# 04ddr3.net
KiCad netlist of a schematic drawn in Altium Designer
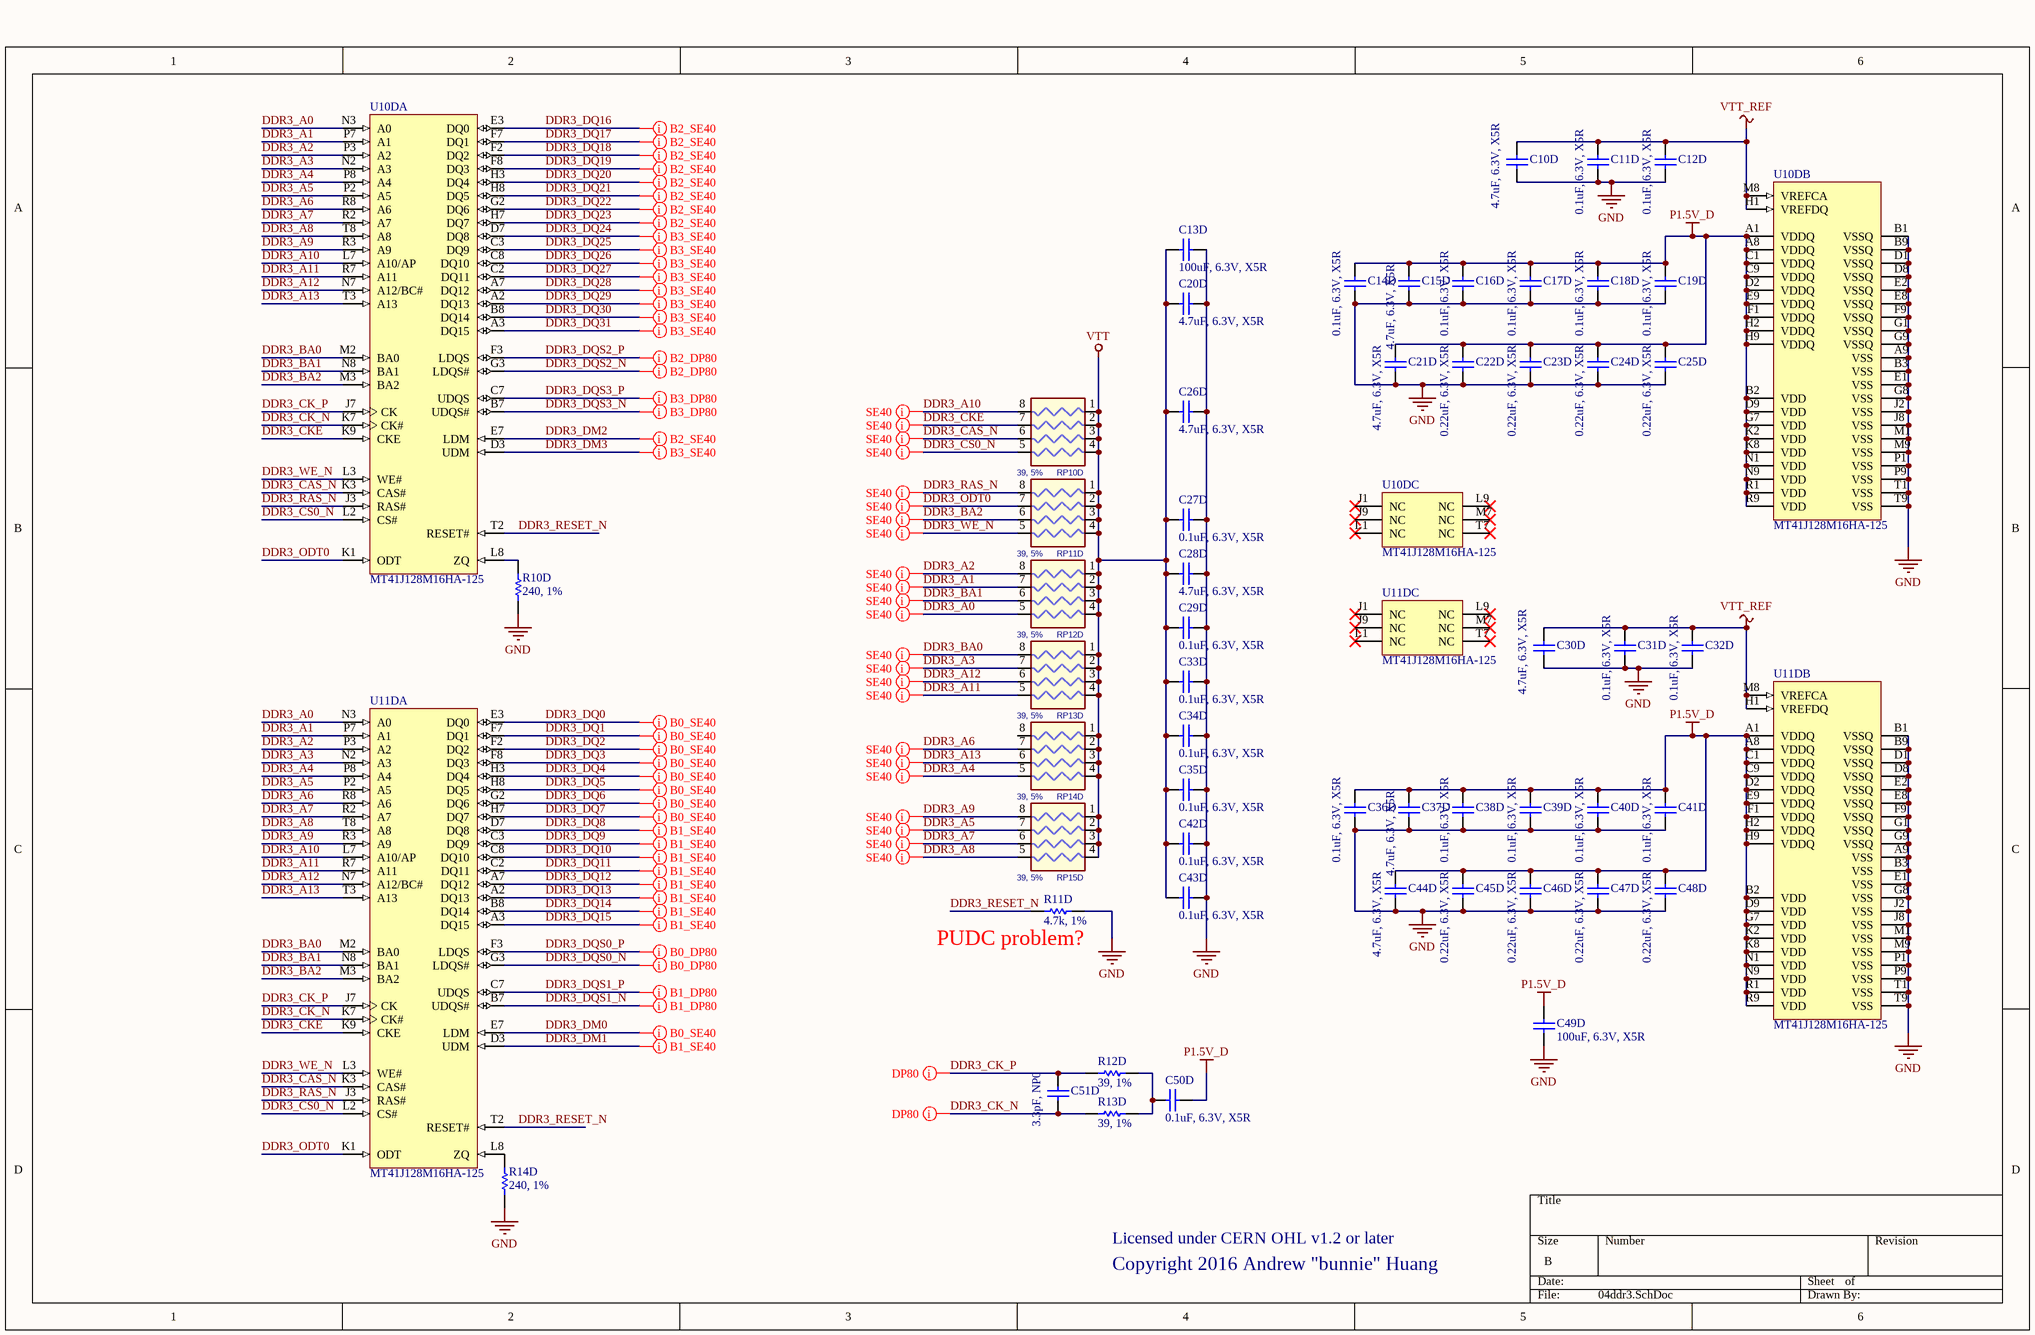
[diagram p0: 04ddr3.SchDoc]

(export (version "E")
  (design (tool "Eeschema 10.0.6"))
  (components
    (comp (ref "C10D")
      (value "4.7uF, 6.3V, X5R")
      (footprint "CAPC1005N")
      (description "Capacitor (Semiconductor SIM Model)")
      (fields (field (name "MPN") "CL05A475MQ5NQNC"))
      (libsource (lib "Miscellaneous Devices") (part "Cap Semi"))
    )
    (comp (ref "C11D")
      (value "0.1uF, 6.3V, X5R")
      (footprint "CAPC0603X03L")
      (description "Capacitor (Semiconductor SIM Model)")
      (fields (field (name "MPN") "CL03A104KQ3NNNC"))
      (libsource (lib "Miscellaneous Devices") (part "Cap Semi"))
    )
    (comp (ref "C12D")
      (value "0.1uF, 6.3V, X5R")
      (footprint "CAPC0603X03L")
      (description "Capacitor (Semiconductor SIM Model)")
      (fields (field (name "MPN") "CL03A104KQ3NNNC"))
      (libsource (lib "Miscellaneous Devices") (part "Cap Semi"))
    )
    (comp (ref "C13D")
      (value "100uF, 6.3V, X5R")
      (footprint "CAPC3216N")
      (description "Capacitor (Semiconductor SIM Model)")
      (fields (field (name "MPN") "CL31A107MQHNNNE"))
      (libsource (lib "Miscellaneous Devices") (part "Cap Semi"))
    )
    (comp (ref "C14D")
      (value "0.1uF, 6.3V, X5R")
      (footprint "CAPC0603X03L")
      (description "Capacitor (Semiconductor SIM Model)")
      (fields (field (name "MPN") "CL03A104KQ3NNNC"))
      (libsource (lib "Miscellaneous Devices") (part "Cap Semi"))
    )
    (comp (ref "C15D")
      (value "4.7uF, 6.3V, X5R")
      (footprint "CAPC1005N")
      (description "Capacitor (Semiconductor SIM Model)")
      (fields (field (name "MPN") "CL05A475MQ5NQNC"))
      (libsource (lib "Miscellaneous Devices") (part "Cap Semi"))
    )
    (comp (ref "C16D")
      (value "0.1uF, 6.3V, X5R")
      (footprint "CAPC0603X03L")
      (description "Capacitor (Semiconductor SIM Model)")
      (fields (field (name "MPN") "CL03A104KQ3NNNC"))
      (libsource (lib "Miscellaneous Devices") (part "Cap Semi"))
    )
    (comp (ref "C17D")
      (value "0.1uF, 6.3V, X5R")
      (footprint "CAPC0603X03L")
      (description "Capacitor (Semiconductor SIM Model)")
      (fields (field (name "MPN") "CL03A104KQ3NNNC"))
      (libsource (lib "Miscellaneous Devices") (part "Cap Semi"))
    )
    (comp (ref "C18D")
      (value "0.1uF, 6.3V, X5R")
      (footprint "CAPC0603X03L")
      (description "Capacitor (Semiconductor SIM Model)")
      (fields (field (name "MPN") "CL03A104KQ3NNNC"))
      (libsource (lib "Miscellaneous Devices") (part "Cap Semi"))
    )
    (comp (ref "C19D")
      (value "0.1uF, 6.3V, X5R")
      (footprint "CAPC0603X03L")
      (description "Capacitor (Semiconductor SIM Model)")
      (fields (field (name "MPN") "CL03A104KQ3NNNC"))
      (libsource (lib "Miscellaneous Devices") (part "Cap Semi"))
    )
    (comp (ref "C20D")
      (value "4.7uF, 6.3V, X5R")
      (footprint "CAPC1005N")
      (description "Capacitor (Semiconductor SIM Model)")
      (fields (field (name "MPN") "CL05A475MQ5NQNC"))
      (libsource (lib "Miscellaneous Devices") (part "Cap Semi"))
    )
    (comp (ref "C21D")
      (value "4.7uF, 6.3V, X5R")
      (footprint "CAPC1005N")
      (description "Capacitor (Semiconductor SIM Model)")
      (fields (field (name "MPN") "CL05A475MQ5NQNC"))
      (libsource (lib "Miscellaneous Devices") (part "Cap Semi"))
    )
    (comp (ref "C22D")
      (value "0.22uF, 6.3V, X5R")
      (footprint "CAPC0603X03L")
      (description "Capacitor (Semiconductor SIM Model)")
      (fields (field (name "MPN") "CL03A224MQ3NNNC"))
      (libsource (lib "Miscellaneous Devices") (part "Cap Semi"))
    )
    (comp (ref "C23D")
      (value "0.22uF, 6.3V, X5R")
      (footprint "CAPC0603X03L")
      (description "Capacitor (Semiconductor SIM Model)")
      (fields (field (name "MPN") "CL03A224MQ3NNNC"))
      (libsource (lib "Miscellaneous Devices") (part "Cap Semi"))
    )
    (comp (ref "C24D")
      (value "0.22uF, 6.3V, X5R")
      (footprint "CAPC0603X03L")
      (description "Capacitor (Semiconductor SIM Model)")
      (fields (field (name "MPN") "CL03A224MQ3NNNC"))
      (libsource (lib "Miscellaneous Devices") (part "Cap Semi"))
    )
    (comp (ref "C25D")
      (value "0.22uF, 6.3V, X5R")
      (footprint "CAPC0603X03L")
      (description "Capacitor (Semiconductor SIM Model)")
      (fields (field (name "MPN") "CL03A224MQ3NNNC"))
      (libsource (lib "Miscellaneous Devices") (part "Cap Semi"))
    )
    (comp (ref "C26D")
      (value "4.7uF, 6.3V, X5R")
      (footprint "CAPC1005N")
      (description "Capacitor (Semiconductor SIM Model)")
      (fields (field (name "MPN") "CL05A475MQ5NQNC"))
      (libsource (lib "Miscellaneous Devices") (part "Cap Semi"))
    )
    (comp (ref "C27D")
      (value "0.1uF, 6.3V, X5R")
      (footprint "CAPC0603X03L")
      (description "Capacitor (Semiconductor SIM Model)")
      (fields (field (name "MPN") "CL03A104KQ3NNNC"))
      (libsource (lib "Miscellaneous Devices") (part "Cap Semi"))
    )
    (comp (ref "C28D")
      (value "4.7uF, 6.3V, X5R")
      (footprint "CAPC1005N")
      (description "Capacitor (Semiconductor SIM Model)")
      (fields (field (name "MPN") "CL05A475MQ5NQNC"))
      (libsource (lib "Miscellaneous Devices") (part "Cap Semi"))
    )
    (comp (ref "C29D")
      (value "0.1uF, 6.3V, X5R")
      (footprint "CAPC0603X03L")
      (description "Capacitor (Semiconductor SIM Model)")
      (fields (field (name "MPN") "CL03A104KQ3NNNC"))
      (libsource (lib "Miscellaneous Devices") (part "Cap Semi"))
    )
    (comp (ref "C30D")
      (value "4.7uF, 6.3V, X5R")
      (footprint "CAPC1005N")
      (description "Capacitor (Semiconductor SIM Model)")
      (fields (field (name "MPN") "CL05A475MQ5NQNC"))
      (libsource (lib "Miscellaneous Devices") (part "Cap Semi"))
    )
    (comp (ref "C31D")
      (value "0.1uF, 6.3V, X5R")
      (footprint "CAPC0603X03L")
      (description "Capacitor (Semiconductor SIM Model)")
      (fields (field (name "MPN") "CL03A104KQ3NNNC"))
      (libsource (lib "Miscellaneous Devices") (part "Cap Semi"))
    )
    (comp (ref "C32D")
      (value "0.1uF, 6.3V, X5R")
      (footprint "CAPC0603X03L")
      (description "Capacitor (Semiconductor SIM Model)")
      (fields (field (name "MPN") "CL03A104KQ3NNNC"))
      (libsource (lib "Miscellaneous Devices") (part "Cap Semi"))
    )
    (comp (ref "C33D")
      (value "0.1uF, 6.3V, X5R")
      (footprint "CAPC0603X03L")
      (description "Capacitor (Semiconductor SIM Model)")
      (fields (field (name "MPN") "CL03A104KQ3NNNC"))
      (libsource (lib "Miscellaneous Devices") (part "Cap Semi"))
    )
    (comp (ref "C34D")
      (value "0.1uF, 6.3V, X5R")
      (footprint "CAPC0603X03L")
      (description "Capacitor (Semiconductor SIM Model)")
      (fields (field (name "MPN") "CL03A104KQ3NNNC"))
      (libsource (lib "Miscellaneous Devices") (part "Cap Semi"))
    )
    (comp (ref "C35D")
      (value "0.1uF, 6.3V, X5R")
      (footprint "CAPC0603X03L")
      (description "Capacitor (Semiconductor SIM Model)")
      (fields (field (name "MPN") "CL03A104KQ3NNNC"))
      (libsource (lib "Miscellaneous Devices") (part "Cap Semi"))
    )
    (comp (ref "C36D")
      (value "0.1uF, 6.3V, X5R")
      (footprint "CAPC0603X03L")
      (description "Capacitor (Semiconductor SIM Model)")
      (fields (field (name "MPN") "CL03A104KQ3NNNC"))
      (libsource (lib "Miscellaneous Devices") (part "Cap Semi"))
    )
    (comp (ref "C37D")
      (value "4.7uF, 6.3V, X5R")
      (footprint "CAPC1005N")
      (description "Capacitor (Semiconductor SIM Model)")
      (fields (field (name "MPN") "CL05A475MQ5NQNC"))
      (libsource (lib "Miscellaneous Devices") (part "Cap Semi"))
    )
    (comp (ref "C38D")
      (value "0.1uF, 6.3V, X5R")
      (footprint "CAPC0603X03L")
      (description "Capacitor (Semiconductor SIM Model)")
      (fields (field (name "MPN") "CL03A104KQ3NNNC"))
      (libsource (lib "Miscellaneous Devices") (part "Cap Semi"))
    )
    (comp (ref "C39D")
      (value "0.1uF, 6.3V, X5R")
      (footprint "CAPC0603X03L")
      (description "Capacitor (Semiconductor SIM Model)")
      (fields (field (name "MPN") "CL03A104KQ3NNNC"))
      (libsource (lib "Miscellaneous Devices") (part "Cap Semi"))
    )
    (comp (ref "C40D")
      (value "0.1uF, 6.3V, X5R")
      (footprint "CAPC0603X03L")
      (description "Capacitor (Semiconductor SIM Model)")
      (fields (field (name "MPN") "CL03A104KQ3NNNC"))
      (libsource (lib "Miscellaneous Devices") (part "Cap Semi"))
    )
    (comp (ref "C41D")
      (value "0.1uF, 6.3V, X5R")
      (footprint "CAPC0603X03L")
      (description "Capacitor (Semiconductor SIM Model)")
      (fields (field (name "MPN") "CL03A104KQ3NNNC"))
      (libsource (lib "Miscellaneous Devices") (part "Cap Semi"))
    )
    (comp (ref "C42D")
      (value "0.1uF, 6.3V, X5R")
      (footprint "CAPC0603X03L")
      (description "Capacitor (Semiconductor SIM Model)")
      (fields (field (name "MPN") "CL03A104KQ3NNNC"))
      (libsource (lib "Miscellaneous Devices") (part "Cap Semi"))
    )
    (comp (ref "C43D")
      (value "0.1uF, 6.3V, X5R")
      (footprint "CAPC0603X03L")
      (description "Capacitor (Semiconductor SIM Model)")
      (fields (field (name "MPN") "CL03A104KQ3NNNC"))
      (libsource (lib "Miscellaneous Devices") (part "Cap Semi"))
    )
    (comp (ref "C44D")
      (value "4.7uF, 6.3V, X5R")
      (footprint "CAPC1005N")
      (description "Capacitor (Semiconductor SIM Model)")
      (fields (field (name "MPN") "CL05A475MQ5NQNC"))
      (libsource (lib "Miscellaneous Devices") (part "Cap Semi"))
    )
    (comp (ref "C45D")
      (value "0.22uF, 6.3V, X5R")
      (footprint "CAPC0603X03L")
      (description "Capacitor (Semiconductor SIM Model)")
      (fields (field (name "MPN") "CL03A224MQ3NNNC"))
      (libsource (lib "Miscellaneous Devices") (part "Cap Semi"))
    )
    (comp (ref "C46D")
      (value "0.22uF, 6.3V, X5R")
      (footprint "CAPC0603X03L")
      (description "Capacitor (Semiconductor SIM Model)")
      (fields (field (name "MPN") "CL03A224MQ3NNNC"))
      (libsource (lib "Miscellaneous Devices") (part "Cap Semi"))
    )
    (comp (ref "C47D")
      (value "0.22uF, 6.3V, X5R")
      (footprint "CAPC0603X03L")
      (description "Capacitor (Semiconductor SIM Model)")
      (fields (field (name "MPN") "CL03A224MQ3NNNC"))
      (libsource (lib "Miscellaneous Devices") (part "Cap Semi"))
    )
    (comp (ref "C48D")
      (value "0.22uF, 6.3V, X5R")
      (footprint "CAPC0603X03L")
      (description "Capacitor (Semiconductor SIM Model)")
      (fields (field (name "MPN") "CL03A224MQ3NNNC"))
      (libsource (lib "Miscellaneous Devices") (part "Cap Semi"))
    )
    (comp (ref "C49D")
      (value "100uF, 6.3V, X5R")
      (footprint "CAPC3216N")
      (description "Capacitor (Semiconductor SIM Model)")
      (fields (field (name "MPN") "CL31A107MQHNNNE"))
      (libsource (lib "Miscellaneous Devices") (part "Cap Semi"))
    )
    (comp (ref "C50D")
      (value "0.1uF, 6.3V, X5R")
      (footprint "CAPC0603X03L")
      (description "Capacitor (Semiconductor SIM Model)")
      (fields (field (name "MPN") "CL03A104KQ3NNNC"))
      (libsource (lib "Miscellaneous Devices") (part "Cap Semi"))
    )
    (comp (ref "C51D")
      (value "3.3pF, NP0")
      (footprint "CAPC0603X03L")
      (description "Capacitor (Semiconductor SIM Model)")
      (fields (field (name "MPN") "GRM0335C1H3R3CA01D"))
      (libsource (lib "Miscellaneous Devices") (part "Cap Semi"))
    )
    (comp (ref "R10D")
      (value "240, 1%")
      (footprint "CAPC0603X03L")
      (description "Resistor")
      (fields (field (name "MPN") "ANY"))
      (libsource (lib "Miscellaneous Devices") (part "Res1"))
    )
    (comp (ref "R11D")
      (value "4.7k, 1%")
      (footprint "RESC1005N")
      (description "Resistor")
      (fields (field (name "MPN") "ANY"))
      (libsource (lib "Miscellaneous Devices") (part "Res1"))
    )
    (comp (ref "R12D")
      (value "39, 1%")
      (footprint "RESC1005N")
      (description "Resistor")
      (fields (field (name "MPN") "ANY"))
      (libsource (lib "Miscellaneous Devices") (part "Res1"))
    )
    (comp (ref "R13D")
      (value "39, 1%")
      (footprint "RESC1005N")
      (description "Resistor")
      (fields (field (name "MPN") "ANY"))
      (libsource (lib "Miscellaneous Devices") (part "Res1"))
    )
    (comp (ref "R14D")
      (value "240, 1%")
      (footprint "CAPC0603X03L")
      (description "Resistor")
      (fields (field (name "MPN") "ANY"))
      (libsource (lib "Miscellaneous Devices") (part "Res1"))
    )
    (comp (ref "RP10D")
      (value "39, 5%")
      (fields (field (name "MPN") "RP104PJ390CS"))
      (libsource (lib "*") (part "RPACK4"))
    )
    (comp (ref "RP11D")
      (value "39, 5%")
      (fields (field (name "MPN") "RP104PJ390CS"))
      (libsource (lib "*") (part "RPACK4"))
    )
    (comp (ref "RP12D")
      (value "39, 5%")
      (fields (field (name "MPN") "RP104PJ390CS"))
      (libsource (lib "*") (part "RPACK4"))
    )
    (comp (ref "RP13D")
      (value "39, 5%")
      (fields (field (name "MPN") "RP104PJ390CS"))
      (libsource (lib "*") (part "RPACK4"))
    )
    (comp (ref "RP14D")
      (value "39, 5%")
      (fields (field (name "MPN") "RP104PJ390CS"))
      (libsource (lib "*") (part "RPACK4"))
    )
    (comp (ref "RP15D")
      (value "39, 5%")
      (fields (field (name "MPN") "RP104PJ390CS"))
      (libsource (lib "*") (part "RPACK4"))
    )
    (comp (ref "U10D")
      (value "MT41J128M16HA-125")
      (footprint "MICT-HA-96")
      (description "2Gb DDR3-1600 SDRAM, 128Mb x 16, 1.25ns, 1.5V, 0 to 95 degC, 96-Ball FBGA, Pb-Free")
      (fields (field (name "VOLTAGE") "1.5V ") (field (name "MPN") "MT41J128M16JT-125:K"))
      (libsource (lib "Micron Memory DDR3 SDRAM") (part "MT41J128M16HA-125"))
    )
    (comp (ref "U11D")
      (value "MT41J128M16HA-125")
      (footprint "MICT-HA-96")
      (description "2Gb DDR3-1600 SDRAM, 128Mb x 16, 1.25ns, 1.5V, 0 to 95 degC, 96-Ball FBGA, Pb-Free")
      (fields (field (name "VOLTAGE") "1.5V ") (field (name "MPN") "MT41J128M16JT-125:K"))
      (libsource (lib "Micron Memory DDR3 SDRAM") (part "MT41J128M16HA-125"))
    )
  )
  (nets
    (net (code "1") (name "/DDR3_A0") (class "Default")
      (node (ref "RP12D") (pin "5") (pinfunction "R42_5") (pintype "passive"))
      (node (ref "U10D") (pin "N3") (pinfunction "A0_N3") (pintype "input"))
      (node (ref "U11D") (pin "N3") (pinfunction "A0_N3") (pintype "input"))
    )
    (net (code "2") (name "/DDR3_A1") (class "Default")
      (node (ref "RP12D") (pin "7") (pinfunction "R22_7") (pintype "passive"))
      (node (ref "U10D") (pin "P7") (pinfunction "A1_P7") (pintype "input"))
      (node (ref "U11D") (pin "P7") (pinfunction "A1_P7") (pintype "input"))
    )
    (net (code "3") (name "/DDR3_A2") (class "Default")
      (node (ref "RP12D") (pin "8") (pinfunction "R12_8") (pintype "passive"))
      (node (ref "U10D") (pin "P3") (pinfunction "A2_P3") (pintype "input"))
      (node (ref "U11D") (pin "P3") (pinfunction "A2_P3") (pintype "input"))
    )
    (net (code "4") (name "/DDR3_A3") (class "Default")
      (node (ref "RP13D") (pin "7") (pinfunction "R22_7") (pintype "passive"))
      (node (ref "U10D") (pin "N2") (pinfunction "A3_N2") (pintype "input"))
      (node (ref "U11D") (pin "N2") (pinfunction "A3_N2") (pintype "input"))
    )
    (net (code "5") (name "/DDR3_A4") (class "Default")
      (node (ref "RP14D") (pin "5") (pinfunction "R42_5") (pintype "passive"))
      (node (ref "U10D") (pin "P8") (pinfunction "A4_P8") (pintype "input"))
      (node (ref "U11D") (pin "P8") (pinfunction "A4_P8") (pintype "input"))
    )
    (net (code "6") (name "/DDR3_A5") (class "Default")
      (node (ref "RP15D") (pin "7") (pinfunction "R22_7") (pintype "passive"))
      (node (ref "U10D") (pin "P2") (pinfunction "A5_P2") (pintype "input"))
      (node (ref "U11D") (pin "P2") (pinfunction "A5_P2") (pintype "input"))
    )
    (net (code "7") (name "/DDR3_A6") (class "Default")
      (node (ref "RP14D") (pin "7") (pinfunction "R22_7") (pintype "passive"))
      (node (ref "U10D") (pin "R8") (pinfunction "A6_R8") (pintype "input"))
      (node (ref "U11D") (pin "R8") (pinfunction "A6_R8") (pintype "input"))
    )
    (net (code "8") (name "/DDR3_A7") (class "Default")
      (node (ref "RP15D") (pin "6") (pinfunction "R32_6") (pintype "passive"))
      (node (ref "U10D") (pin "R2") (pinfunction "A7_R2") (pintype "input"))
      (node (ref "U11D") (pin "R2") (pinfunction "A7_R2") (pintype "input"))
    )
    (net (code "9") (name "/DDR3_A8") (class "Default")
      (node (ref "RP15D") (pin "5") (pinfunction "R42_5") (pintype "passive"))
      (node (ref "U10D") (pin "T8") (pinfunction "A8_T8") (pintype "input"))
      (node (ref "U11D") (pin "T8") (pinfunction "A8_T8") (pintype "input"))
    )
    (net (code "10") (name "/DDR3_A9") (class "Default")
      (node (ref "RP15D") (pin "8") (pinfunction "R12_8") (pintype "passive"))
      (node (ref "U10D") (pin "R3") (pinfunction "A9_R3") (pintype "input"))
      (node (ref "U11D") (pin "R3") (pinfunction "A9_R3") (pintype "input"))
    )
    (net (code "11") (name "/DDR3_A10") (class "Default")
      (node (ref "RP10D") (pin "8") (pinfunction "R12_8") (pintype "passive"))
      (node (ref "U10D") (pin "L7") (pinfunction "A10/AP_L7") (pintype "input"))
      (node (ref "U11D") (pin "L7") (pinfunction "A10/AP_L7") (pintype "input"))
    )
    (net (code "12") (name "/DDR3_A11") (class "Default")
      (node (ref "RP13D") (pin "5") (pinfunction "R42_5") (pintype "passive"))
      (node (ref "U10D") (pin "R7") (pinfunction "A11_R7") (pintype "input"))
      (node (ref "U11D") (pin "R7") (pinfunction "A11_R7") (pintype "input"))
    )
    (net (code "13") (name "/DDR3_A12") (class "Default")
      (node (ref "RP13D") (pin "6") (pinfunction "R32_6") (pintype "passive"))
      (node (ref "U10D") (pin "N7") (pinfunction "A12/BC#_N7") (pintype "input"))
      (node (ref "U11D") (pin "N7") (pinfunction "A12/BC#_N7") (pintype "input"))
    )
    (net (code "14") (name "/DDR3_A13") (class "Default")
      (node (ref "RP14D") (pin "6") (pinfunction "R32_6") (pintype "passive"))
      (node (ref "U10D") (pin "T3") (pinfunction "A13_T3") (pintype "input"))
      (node (ref "U11D") (pin "T3") (pinfunction "A13_T3") (pintype "input"))
    )
    (net (code "15") (name "/DDR3_BA0") (class "Default")
      (node (ref "RP13D") (pin "8") (pinfunction "R12_8") (pintype "passive"))
      (node (ref "U10D") (pin "M2") (pinfunction "BA0_M2") (pintype "input"))
      (node (ref "U11D") (pin "M2") (pinfunction "BA0_M2") (pintype "input"))
    )
    (net (code "16") (name "/DDR3_BA1") (class "Default")
      (node (ref "RP12D") (pin "6") (pinfunction "R32_6") (pintype "passive"))
      (node (ref "U10D") (pin "N8") (pinfunction "BA1_N8") (pintype "input"))
      (node (ref "U11D") (pin "N8") (pinfunction "BA1_N8") (pintype "input"))
    )
    (net (code "17") (name "/DDR3_BA2") (class "Default")
      (node (ref "RP11D") (pin "6") (pinfunction "R32_6") (pintype "passive"))
      (node (ref "U10D") (pin "M3") (pinfunction "BA2_M3") (pintype "input"))
      (node (ref "U11D") (pin "M3") (pinfunction "BA2_M3") (pintype "input"))
    )
    (net (code "18") (name "/DDR3_CAS_N") (class "Default")
      (node (ref "RP10D") (pin "6") (pinfunction "R32_6") (pintype "passive"))
      (node (ref "U10D") (pin "K3") (pinfunction "CAS#_K3") (pintype "input"))
      (node (ref "U11D") (pin "K3") (pinfunction "CAS#_K3") (pintype "input"))
    )
    (net (code "19") (name "/DDR3_CKE") (class "Default")
      (node (ref "RP10D") (pin "7") (pinfunction "R22_7") (pintype "passive"))
      (node (ref "U10D") (pin "K9") (pinfunction "CKE_K9") (pintype "input"))
      (node (ref "U11D") (pin "K9") (pinfunction "CKE_K9") (pintype "input"))
    )
    (net (code "20") (name "/DDR3_CK_N") (class "Default")
      (node (ref "C51D") (pin "1") (pinfunction "1_1") (pintype "passive"))
      (node (ref "R13D") (pin "1") (pinfunction "1_1") (pintype "passive"))
      (node (ref "U10D") (pin "K7") (pinfunction "CK#_K7") (pintype "input"))
      (node (ref "U11D") (pin "K7") (pinfunction "CK#_K7") (pintype "input"))
    )
    (net (code "21") (name "/DDR3_CK_P") (class "Default")
      (node (ref "C51D") (pin "2") (pinfunction "2_2") (pintype "passive"))
      (node (ref "R12D") (pin "1") (pinfunction "1_1") (pintype "passive"))
      (node (ref "U10D") (pin "J7") (pinfunction "CK_J7") (pintype "input"))
      (node (ref "U11D") (pin "J7") (pinfunction "CK_J7") (pintype "input"))
    )
    (net (code "22") (name "/DDR3_CS0_N") (class "Default")
      (node (ref "RP10D") (pin "5") (pinfunction "R42_5") (pintype "passive"))
      (node (ref "U10D") (pin "L2") (pinfunction "CS#_L2") (pintype "input"))
      (node (ref "U11D") (pin "L2") (pinfunction "CS#_L2") (pintype "input"))
    )
    (net (code "23") (name "/DDR3_DM0") (class "Default")
      (node (ref "U11D") (pin "E7") (pinfunction "LDM_E7") (pintype "input"))
    )
    (net (code "24") (name "/DDR3_DM1") (class "Default")
      (node (ref "U11D") (pin "D3") (pinfunction "UDM_D3") (pintype "input"))
    )
    (net (code "25") (name "/DDR3_DM2") (class "Default")
      (node (ref "U10D") (pin "E7") (pinfunction "LDM_E7") (pintype "input"))
    )
    (net (code "26") (name "/DDR3_DM3") (class "Default")
      (node (ref "U10D") (pin "D3") (pinfunction "UDM_D3") (pintype "input"))
    )
    (net (code "27") (name "/DDR3_DQ0") (class "Default")
      (node (ref "U11D") (pin "E3") (pinfunction "DQ0_E3") (pintype "bidirectional"))
    )
    (net (code "28") (name "/DDR3_DQ1") (class "Default")
      (node (ref "U11D") (pin "F7") (pinfunction "DQ1_F7") (pintype "bidirectional"))
    )
    (net (code "29") (name "/DDR3_DQ2") (class "Default")
      (node (ref "U11D") (pin "F2") (pinfunction "DQ2_F2") (pintype "bidirectional"))
    )
    (net (code "30") (name "/DDR3_DQ3") (class "Default")
      (node (ref "U11D") (pin "F8") (pinfunction "DQ3_F8") (pintype "bidirectional"))
    )
    (net (code "31") (name "/DDR3_DQ4") (class "Default")
      (node (ref "U11D") (pin "H3") (pinfunction "DQ4_H3") (pintype "bidirectional"))
    )
    (net (code "32") (name "/DDR3_DQ5") (class "Default")
      (node (ref "U11D") (pin "H8") (pinfunction "DQ5_H8") (pintype "bidirectional"))
    )
    (net (code "33") (name "/DDR3_DQ6") (class "Default")
      (node (ref "U11D") (pin "G2") (pinfunction "DQ6_G2") (pintype "bidirectional"))
    )
    (net (code "34") (name "/DDR3_DQ7") (class "Default")
      (node (ref "U11D") (pin "H7") (pinfunction "DQ7_H7") (pintype "bidirectional"))
    )
    (net (code "35") (name "/DDR3_DQ8") (class "Default")
      (node (ref "U11D") (pin "D7") (pinfunction "DQ8_D7") (pintype "bidirectional"))
    )
    (net (code "36") (name "/DDR3_DQ9") (class "Default")
      (node (ref "U11D") (pin "C3") (pinfunction "DQ9_C3") (pintype "bidirectional"))
    )
    (net (code "37") (name "/DDR3_DQ10") (class "Default")
      (node (ref "U11D") (pin "C8") (pinfunction "DQ10_C8") (pintype "bidirectional"))
    )
    (net (code "38") (name "/DDR3_DQ11") (class "Default")
      (node (ref "U11D") (pin "C2") (pinfunction "DQ11_C2") (pintype "bidirectional"))
    )
    (net (code "39") (name "/DDR3_DQ12") (class "Default")
      (node (ref "U11D") (pin "A7") (pinfunction "DQ12_A7") (pintype "bidirectional"))
    )
    (net (code "40") (name "/DDR3_DQ13") (class "Default")
      (node (ref "U11D") (pin "A2") (pinfunction "DQ13_A2") (pintype "bidirectional"))
    )
    (net (code "41") (name "/DDR3_DQ14") (class "Default")
      (node (ref "U11D") (pin "B8") (pinfunction "DQ14_B8") (pintype "bidirectional"))
    )
    (net (code "42") (name "/DDR3_DQ15") (class "Default")
      (node (ref "U11D") (pin "A3") (pinfunction "DQ15_A3") (pintype "bidirectional"))
    )
    (net (code "43") (name "/DDR3_DQ16") (class "Default")
      (node (ref "U10D") (pin "E3") (pinfunction "DQ0_E3") (pintype "bidirectional"))
    )
    (net (code "44") (name "/DDR3_DQ17") (class "Default")
      (node (ref "U10D") (pin "F7") (pinfunction "DQ1_F7") (pintype "bidirectional"))
    )
    (net (code "45") (name "/DDR3_DQ18") (class "Default")
      (node (ref "U10D") (pin "F2") (pinfunction "DQ2_F2") (pintype "bidirectional"))
    )
    (net (code "46") (name "/DDR3_DQ19") (class "Default")
      (node (ref "U10D") (pin "F8") (pinfunction "DQ3_F8") (pintype "bidirectional"))
    )
    (net (code "47") (name "/DDR3_DQ20") (class "Default")
      (node (ref "U10D") (pin "H3") (pinfunction "DQ4_H3") (pintype "bidirectional"))
    )
    (net (code "48") (name "/DDR3_DQ21") (class "Default")
      (node (ref "U10D") (pin "H8") (pinfunction "DQ5_H8") (pintype "bidirectional"))
    )
    (net (code "49") (name "/DDR3_DQ22") (class "Default")
      (node (ref "U10D") (pin "G2") (pinfunction "DQ6_G2") (pintype "bidirectional"))
    )
    (net (code "50") (name "/DDR3_DQ23") (class "Default")
      (node (ref "U10D") (pin "H7") (pinfunction "DQ7_H7") (pintype "bidirectional"))
    )
    (net (code "51") (name "/DDR3_DQ24") (class "Default")
      (node (ref "U10D") (pin "D7") (pinfunction "DQ8_D7") (pintype "bidirectional"))
    )
    (net (code "52") (name "/DDR3_DQ25") (class "Default")
      (node (ref "U10D") (pin "C3") (pinfunction "DQ9_C3") (pintype "bidirectional"))
    )
    (net (code "53") (name "/DDR3_DQ26") (class "Default")
      (node (ref "U10D") (pin "C8") (pinfunction "DQ10_C8") (pintype "bidirectional"))
    )
    (net (code "54") (name "/DDR3_DQ27") (class "Default")
      (node (ref "U10D") (pin "C2") (pinfunction "DQ11_C2") (pintype "bidirectional"))
    )
    (net (code "55") (name "/DDR3_DQ28") (class "Default")
      (node (ref "U10D") (pin "A7") (pinfunction "DQ12_A7") (pintype "bidirectional"))
    )
    (net (code "56") (name "/DDR3_DQ29") (class "Default")
      (node (ref "U10D") (pin "A2") (pinfunction "DQ13_A2") (pintype "bidirectional"))
    )
    (net (code "57") (name "/DDR3_DQ30") (class "Default")
      (node (ref "U10D") (pin "B8") (pinfunction "DQ14_B8") (pintype "bidirectional"))
    )
    (net (code "58") (name "/DDR3_DQ31") (class "Default")
      (node (ref "U10D") (pin "A3") (pinfunction "DQ15_A3") (pintype "bidirectional"))
    )
    (net (code "59") (name "/DDR3_DQS0_N") (class "Default")
      (node (ref "U11D") (pin "G3") (pinfunction "LDQS#_G3") (pintype "bidirectional"))
    )
    (net (code "60") (name "/DDR3_DQS0_P") (class "Default")
      (node (ref "U11D") (pin "F3") (pinfunction "LDQS_F3") (pintype "bidirectional"))
    )
    (net (code "61") (name "/DDR3_DQS1_N") (class "Default")
      (node (ref "U11D") (pin "B7") (pinfunction "UDQS#_B7") (pintype "bidirectional"))
    )
    (net (code "62") (name "/DDR3_DQS1_P") (class "Default")
      (node (ref "U11D") (pin "C7") (pinfunction "UDQS_C7") (pintype "bidirectional"))
    )
    (net (code "63") (name "/DDR3_DQS2_N") (class "Default")
      (node (ref "U10D") (pin "G3") (pinfunction "LDQS#_G3") (pintype "bidirectional"))
    )
    (net (code "64") (name "/DDR3_DQS2_P") (class "Default")
      (node (ref "U10D") (pin "F3") (pinfunction "LDQS_F3") (pintype "bidirectional"))
    )
    (net (code "65") (name "/DDR3_DQS3_N") (class "Default")
      (node (ref "U10D") (pin "B7") (pinfunction "UDQS#_B7") (pintype "bidirectional"))
    )
    (net (code "66") (name "/DDR3_DQS3_P") (class "Default")
      (node (ref "U10D") (pin "C7") (pinfunction "UDQS_C7") (pintype "bidirectional"))
    )
    (net (code "67") (name "/DDR3_ODT0") (class "Default")
      (node (ref "RP11D") (pin "7") (pinfunction "R22_7") (pintype "passive"))
      (node (ref "U10D") (pin "K1") (pinfunction "ODT_K1") (pintype "input"))
      (node (ref "U11D") (pin "K1") (pinfunction "ODT_K1") (pintype "input"))
    )
    (net (code "68") (name "/DDR3_RAS_N") (class "Default")
      (node (ref "RP11D") (pin "8") (pinfunction "R12_8") (pintype "passive"))
      (node (ref "U10D") (pin "J3") (pinfunction "RAS#_J3") (pintype "input"))
      (node (ref "U11D") (pin "J3") (pinfunction "RAS#_J3") (pintype "input"))
    )
    (net (code "69") (name "/DDR3_RESET_N") (class "Default")
      (node (ref "R11D") (pin "2") (pinfunction "2_2") (pintype "passive"))
      (node (ref "U10D") (pin "T2") (pinfunction "RESET#_T2") (pintype "input"))
      (node (ref "U11D") (pin "T2") (pinfunction "RESET#_T2") (pintype "input"))
    )
    (net (code "70") (name "/DDR3_WE_N") (class "Default")
      (node (ref "RP11D") (pin "5") (pinfunction "R42_5") (pintype "passive"))
      (node (ref "U10D") (pin "L3") (pinfunction "WE#_L3") (pintype "input"))
      (node (ref "U11D") (pin "L3") (pinfunction "WE#_L3") (pintype "input"))
    )
    (net (code "71") (name "GND") (class "Default")
      (node (ref "C10D") (pin "1") (pinfunction "1_1") (pintype "passive"))
      (node (ref "C11D") (pin "2") (pinfunction "2_2") (pintype "passive"))
      (node (ref "C12D") (pin "2") (pinfunction "2_2") (pintype "passive"))
      (node (ref "C13D") (pin "2") (pinfunction "2_2") (pintype "passive"))
      (node (ref "C14D") (pin "2") (pinfunction "2_2") (pintype "passive"))
      (node (ref "C15D") (pin "2") (pinfunction "2_2") (pintype "passive"))
      (node (ref "C16D") (pin "2") (pinfunction "2_2") (pintype "passive"))
      (node (ref "C17D") (pin "2") (pinfunction "2_2") (pintype "passive"))
      (node (ref "C18D") (pin "2") (pinfunction "2_2") (pintype "passive"))
      (node (ref "C19D") (pin "2") (pinfunction "2_2") (pintype "passive"))
      (node (ref "C20D") (pin "2") (pinfunction "2_2") (pintype "passive"))
      (node (ref "C21D") (pin "2") (pinfunction "2_2") (pintype "passive"))
      (node (ref "C22D") (pin "2") (pinfunction "2_2") (pintype "passive"))
      (node (ref "C23D") (pin "2") (pinfunction "2_2") (pintype "passive"))
      (node (ref "C24D") (pin "2") (pinfunction "2_2") (pintype "passive"))
      (node (ref "C25D") (pin "2") (pinfunction "2_2") (pintype "passive"))
      (node (ref "C26D") (pin "2") (pinfunction "2_2") (pintype "passive"))
      (node (ref "C27D") (pin "1") (pinfunction "1_1") (pintype "passive"))
      (node (ref "C28D") (pin "2") (pinfunction "2_2") (pintype "passive"))
      (node (ref "C29D") (pin "1") (pinfunction "1_1") (pintype "passive"))
      (node (ref "C30D") (pin "1") (pinfunction "1_1") (pintype "passive"))
      (node (ref "C31D") (pin "2") (pinfunction "2_2") (pintype "passive"))
      (node (ref "C32D") (pin "2") (pinfunction "2_2") (pintype "passive"))
      (node (ref "C33D") (pin "1") (pinfunction "1_1") (pintype "passive"))
      (node (ref "C34D") (pin "1") (pinfunction "1_1") (pintype "passive"))
      (node (ref "C35D") (pin "1") (pinfunction "1_1") (pintype "passive"))
      (node (ref "C36D") (pin "2") (pinfunction "2_2") (pintype "passive"))
      (node (ref "C37D") (pin "2") (pinfunction "2_2") (pintype "passive"))
      (node (ref "C38D") (pin "2") (pinfunction "2_2") (pintype "passive"))
      (node (ref "C39D") (pin "2") (pinfunction "2_2") (pintype "passive"))
      (node (ref "C40D") (pin "2") (pinfunction "2_2") (pintype "passive"))
      (node (ref "C41D") (pin "2") (pinfunction "2_2") (pintype "passive"))
      (node (ref "C42D") (pin "1") (pinfunction "1_1") (pintype "passive"))
      (node (ref "C43D") (pin "1") (pinfunction "1_1") (pintype "passive"))
      (node (ref "C44D") (pin "2") (pinfunction "2_2") (pintype "passive"))
      (node (ref "C45D") (pin "2") (pinfunction "2_2") (pintype "passive"))
      (node (ref "C46D") (pin "2") (pinfunction "2_2") (pintype "passive"))
      (node (ref "C47D") (pin "2") (pinfunction "2_2") (pintype "passive"))
      (node (ref "C48D") (pin "2") (pinfunction "2_2") (pintype "passive"))
      (node (ref "C49D") (pin "1") (pinfunction "1_1") (pintype "passive"))
      (node (ref "R10D") (pin "1") (pinfunction "1_1") (pintype "passive"))
      (node (ref "R11D") (pin "1") (pinfunction "1_1") (pintype "passive"))
      (node (ref "R14D") (pin "1") (pinfunction "1_1") (pintype "passive"))
      (node (ref "U10D") (pin "A9") (pinfunction "VSS_A9") (pintype "power_in"))
      (node (ref "U10D") (pin "B1") (pinfunction "VSSQ_B1") (pintype "power_in"))
      (node (ref "U10D") (pin "B3") (pinfunction "VSS_B3") (pintype "power_in"))
      (node (ref "U10D") (pin "B9") (pinfunction "VSSQ_B9") (pintype "power_in"))
      (node (ref "U10D") (pin "D1") (pinfunction "VSSQ_D1") (pintype "power_in"))
      (node (ref "U10D") (pin "D8") (pinfunction "VSSQ_D8") (pintype "power_in"))
      (node (ref "U10D") (pin "E1") (pinfunction "VSS_E1") (pintype "power_in"))
      (node (ref "U10D") (pin "E2") (pinfunction "VSSQ_E2") (pintype "power_in"))
      (node (ref "U10D") (pin "E8") (pinfunction "VSSQ_E8") (pintype "power_in"))
      (node (ref "U10D") (pin "F9") (pinfunction "VSSQ_F9") (pintype "power_in"))
      (node (ref "U10D") (pin "G1") (pinfunction "VSSQ_G1") (pintype "power_in"))
      (node (ref "U10D") (pin "G8") (pinfunction "VSS_G8") (pintype "power_in"))
      (node (ref "U10D") (pin "G9") (pinfunction "VSSQ_G9") (pintype "power_in"))
      (node (ref "U10D") (pin "J2") (pinfunction "VSS_J2") (pintype "power_in"))
      (node (ref "U10D") (pin "J8") (pinfunction "VSS_J8") (pintype "power_in"))
      (node (ref "U10D") (pin "M1") (pinfunction "VSS_M1") (pintype "power_in"))
      (node (ref "U10D") (pin "M9") (pinfunction "VSS_M9") (pintype "power_in"))
      (node (ref "U10D") (pin "P1") (pinfunction "VSS_P1") (pintype "power_in"))
      (node (ref "U10D") (pin "P9") (pinfunction "VSS_P9") (pintype "power_in"))
      (node (ref "U10D") (pin "T1") (pinfunction "VSS_T1") (pintype "power_in"))
      (node (ref "U10D") (pin "T9") (pinfunction "VSS_T9") (pintype "power_in"))
      (node (ref "U11D") (pin "A9") (pinfunction "VSS_A9") (pintype "power_in"))
      (node (ref "U11D") (pin "B1") (pinfunction "VSSQ_B1") (pintype "power_in"))
      (node (ref "U11D") (pin "B3") (pinfunction "VSS_B3") (pintype "power_in"))
      (node (ref "U11D") (pin "B9") (pinfunction "VSSQ_B9") (pintype "power_in"))
      (node (ref "U11D") (pin "D1") (pinfunction "VSSQ_D1") (pintype "power_in"))
      (node (ref "U11D") (pin "D8") (pinfunction "VSSQ_D8") (pintype "power_in"))
      (node (ref "U11D") (pin "E1") (pinfunction "VSS_E1") (pintype "power_in"))
      (node (ref "U11D") (pin "E2") (pinfunction "VSSQ_E2") (pintype "power_in"))
      (node (ref "U11D") (pin "E8") (pinfunction "VSSQ_E8") (pintype "power_in"))
      (node (ref "U11D") (pin "F9") (pinfunction "VSSQ_F9") (pintype "power_in"))
      (node (ref "U11D") (pin "G1") (pinfunction "VSSQ_G1") (pintype "power_in"))
      (node (ref "U11D") (pin "G8") (pinfunction "VSS_G8") (pintype "power_in"))
      (node (ref "U11D") (pin "G9") (pinfunction "VSSQ_G9") (pintype "power_in"))
      (node (ref "U11D") (pin "J2") (pinfunction "VSS_J2") (pintype "power_in"))
      (node (ref "U11D") (pin "J8") (pinfunction "VSS_J8") (pintype "power_in"))
      (node (ref "U11D") (pin "M1") (pinfunction "VSS_M1") (pintype "power_in"))
      (node (ref "U11D") (pin "M9") (pinfunction "VSS_M9") (pintype "power_in"))
      (node (ref "U11D") (pin "P1") (pinfunction "VSS_P1") (pintype "power_in"))
      (node (ref "U11D") (pin "P9") (pinfunction "VSS_P9") (pintype "power_in"))
      (node (ref "U11D") (pin "T1") (pinfunction "VSS_T1") (pintype "power_in"))
      (node (ref "U11D") (pin "T9") (pinfunction "VSS_T9") (pintype "power_in"))
    )
    (net (code "72") (name "Net-(C50D-Pad2)") (class "Default")
      (node (ref "C50D") (pin "2") (pinfunction "2_2") (pintype "passive"))
      (node (ref "R12D") (pin "2") (pinfunction "2_2") (pintype "passive"))
      (node (ref "R13D") (pin "2") (pinfunction "2_2") (pintype "passive"))
    )
    (net (code "73") (name "Net-(U10DA-ZQ)") (class "Default")
      (node (ref "R10D") (pin "2") (pinfunction "2_2") (pintype "passive"))
      (node (ref "U10D") (pin "L8") (pinfunction "ZQ_L8") (pintype "input"))
    )
    (net (code "74") (name "Net-(U11DA-ZQ)") (class "Default")
      (node (ref "R14D") (pin "2") (pinfunction "2_2") (pintype "passive"))
      (node (ref "U11D") (pin "L8") (pinfunction "ZQ_L8") (pintype "input"))
    )
    (net (code "75") (name "P1.5V_D") (class "Default")
      (node (ref "C14D") (pin "1") (pinfunction "1_1") (pintype "passive"))
      (node (ref "C15D") (pin "1") (pinfunction "1_1") (pintype "passive"))
      (node (ref "C16D") (pin "1") (pinfunction "1_1") (pintype "passive"))
      (node (ref "C17D") (pin "1") (pinfunction "1_1") (pintype "passive"))
      (node (ref "C18D") (pin "1") (pinfunction "1_1") (pintype "passive"))
      (node (ref "C19D") (pin "1") (pinfunction "1_1") (pintype "passive"))
      (node (ref "C21D") (pin "1") (pinfunction "1_1") (pintype "passive"))
      (node (ref "C22D") (pin "1") (pinfunction "1_1") (pintype "passive"))
      (node (ref "C23D") (pin "1") (pinfunction "1_1") (pintype "passive"))
      (node (ref "C24D") (pin "1") (pinfunction "1_1") (pintype "passive"))
      (node (ref "C25D") (pin "1") (pinfunction "1_1") (pintype "passive"))
      (node (ref "C36D") (pin "1") (pinfunction "1_1") (pintype "passive"))
      (node (ref "C37D") (pin "1") (pinfunction "1_1") (pintype "passive"))
      (node (ref "C38D") (pin "1") (pinfunction "1_1") (pintype "passive"))
      (node (ref "C39D") (pin "1") (pinfunction "1_1") (pintype "passive"))
      (node (ref "C40D") (pin "1") (pinfunction "1_1") (pintype "passive"))
      (node (ref "C41D") (pin "1") (pinfunction "1_1") (pintype "passive"))
      (node (ref "C44D") (pin "1") (pinfunction "1_1") (pintype "passive"))
      (node (ref "C45D") (pin "1") (pinfunction "1_1") (pintype "passive"))
      (node (ref "C46D") (pin "1") (pinfunction "1_1") (pintype "passive"))
      (node (ref "C47D") (pin "1") (pinfunction "1_1") (pintype "passive"))
      (node (ref "C48D") (pin "1") (pinfunction "1_1") (pintype "passive"))
      (node (ref "C49D") (pin "2") (pinfunction "2_2") (pintype "passive"))
      (node (ref "C50D") (pin "1") (pinfunction "1_1") (pintype "passive"))
      (node (ref "U10D") (pin "A1") (pinfunction "VDDQ_A1") (pintype "power_in"))
      (node (ref "U10D") (pin "A8") (pinfunction "VDDQ_A8") (pintype "power_in"))
      (node (ref "U10D") (pin "B2") (pinfunction "VDD_B2") (pintype "power_in"))
      (node (ref "U10D") (pin "C1") (pinfunction "VDDQ_C1") (pintype "power_in"))
      (node (ref "U10D") (pin "C9") (pinfunction "VDDQ_C9") (pintype "power_in"))
      (node (ref "U10D") (pin "D2") (pinfunction "VDDQ_D2") (pintype "power_in"))
      (node (ref "U10D") (pin "D9") (pinfunction "VDD_D9") (pintype "power_in"))
      (node (ref "U10D") (pin "E9") (pinfunction "VDDQ_E9") (pintype "power_in"))
      (node (ref "U10D") (pin "F1") (pinfunction "VDDQ_F1") (pintype "power_in"))
      (node (ref "U10D") (pin "G7") (pinfunction "VDD_G7") (pintype "power_in"))
      (node (ref "U10D") (pin "H2") (pinfunction "VDDQ_H2") (pintype "power_in"))
      (node (ref "U10D") (pin "H9") (pinfunction "VDDQ_H9") (pintype "power_in"))
      (node (ref "U10D") (pin "K2") (pinfunction "VDD_K2") (pintype "power_in"))
      (node (ref "U10D") (pin "K8") (pinfunction "VDD_K8") (pintype "power_in"))
      (node (ref "U10D") (pin "N1") (pinfunction "VDD_N1") (pintype "power_in"))
      (node (ref "U10D") (pin "N9") (pinfunction "VDD_N9") (pintype "power_in"))
      (node (ref "U10D") (pin "R1") (pinfunction "VDD_R1") (pintype "power_in"))
      (node (ref "U10D") (pin "R9") (pinfunction "VDD_R9") (pintype "power_in"))
      (node (ref "U11D") (pin "A1") (pinfunction "VDDQ_A1") (pintype "power_in"))
      (node (ref "U11D") (pin "A8") (pinfunction "VDDQ_A8") (pintype "power_in"))
      (node (ref "U11D") (pin "B2") (pinfunction "VDD_B2") (pintype "power_in"))
      (node (ref "U11D") (pin "C1") (pinfunction "VDDQ_C1") (pintype "power_in"))
      (node (ref "U11D") (pin "C9") (pinfunction "VDDQ_C9") (pintype "power_in"))
      (node (ref "U11D") (pin "D2") (pinfunction "VDDQ_D2") (pintype "power_in"))
      (node (ref "U11D") (pin "D9") (pinfunction "VDD_D9") (pintype "power_in"))
      (node (ref "U11D") (pin "E9") (pinfunction "VDDQ_E9") (pintype "power_in"))
      (node (ref "U11D") (pin "F1") (pinfunction "VDDQ_F1") (pintype "power_in"))
      (node (ref "U11D") (pin "G7") (pinfunction "VDD_G7") (pintype "power_in"))
      (node (ref "U11D") (pin "H2") (pinfunction "VDDQ_H2") (pintype "power_in"))
      (node (ref "U11D") (pin "H9") (pinfunction "VDDQ_H9") (pintype "power_in"))
      (node (ref "U11D") (pin "K2") (pinfunction "VDD_K2") (pintype "power_in"))
      (node (ref "U11D") (pin "K8") (pinfunction "VDD_K8") (pintype "power_in"))
      (node (ref "U11D") (pin "N1") (pinfunction "VDD_N1") (pintype "power_in"))
      (node (ref "U11D") (pin "N9") (pinfunction "VDD_N9") (pintype "power_in"))
      (node (ref "U11D") (pin "R1") (pinfunction "VDD_R1") (pintype "power_in"))
      (node (ref "U11D") (pin "R9") (pinfunction "VDD_R9") (pintype "power_in"))
    )
    (net (code "76") (name "VTT") (class "Default")
      (node (ref "C13D") (pin "1") (pinfunction "1_1") (pintype "passive"))
      (node (ref "C20D") (pin "1") (pinfunction "1_1") (pintype "passive"))
      (node (ref "C26D") (pin "1") (pinfunction "1_1") (pintype "passive"))
      (node (ref "C27D") (pin "2") (pinfunction "2_2") (pintype "passive"))
      (node (ref "C28D") (pin "1") (pinfunction "1_1") (pintype "passive"))
      (node (ref "C29D") (pin "2") (pinfunction "2_2") (pintype "passive"))
      (node (ref "C33D") (pin "2") (pinfunction "2_2") (pintype "passive"))
      (node (ref "C34D") (pin "2") (pinfunction "2_2") (pintype "passive"))
      (node (ref "C35D") (pin "2") (pinfunction "2_2") (pintype "passive"))
      (node (ref "C42D") (pin "2") (pinfunction "2_2") (pintype "passive"))
      (node (ref "C43D") (pin "2") (pinfunction "2_2") (pintype "passive"))
      (node (ref "RP10D") (pin "1") (pinfunction "R1_1") (pintype "passive"))
      (node (ref "RP10D") (pin "2") (pinfunction "R2_2") (pintype "passive"))
      (node (ref "RP10D") (pin "3") (pinfunction "R3_3") (pintype "passive"))
      (node (ref "RP10D") (pin "4") (pinfunction "R4_4") (pintype "passive"))
      (node (ref "RP11D") (pin "1") (pinfunction "R1_1") (pintype "passive"))
      (node (ref "RP11D") (pin "2") (pinfunction "R2_2") (pintype "passive"))
      (node (ref "RP11D") (pin "3") (pinfunction "R3_3") (pintype "passive"))
      (node (ref "RP11D") (pin "4") (pinfunction "R4_4") (pintype "passive"))
      (node (ref "RP12D") (pin "1") (pinfunction "R1_1") (pintype "passive"))
      (node (ref "RP12D") (pin "2") (pinfunction "R2_2") (pintype "passive"))
      (node (ref "RP12D") (pin "3") (pinfunction "R3_3") (pintype "passive"))
      (node (ref "RP12D") (pin "4") (pinfunction "R4_4") (pintype "passive"))
      (node (ref "RP13D") (pin "1") (pinfunction "R1_1") (pintype "passive"))
      (node (ref "RP13D") (pin "2") (pinfunction "R2_2") (pintype "passive"))
      (node (ref "RP13D") (pin "3") (pinfunction "R3_3") (pintype "passive"))
      (node (ref "RP13D") (pin "4") (pinfunction "R4_4") (pintype "passive"))
      (node (ref "RP14D") (pin "1") (pinfunction "R1_1") (pintype "passive"))
      (node (ref "RP14D") (pin "2") (pinfunction "R2_2") (pintype "passive"))
      (node (ref "RP14D") (pin "3") (pinfunction "R3_3") (pintype "passive"))
      (node (ref "RP14D") (pin "4") (pinfunction "R4_4") (pintype "passive"))
      (node (ref "RP15D") (pin "1") (pinfunction "R1_1") (pintype "passive"))
      (node (ref "RP15D") (pin "2") (pinfunction "R2_2") (pintype "passive"))
      (node (ref "RP15D") (pin "3") (pinfunction "R3_3") (pintype "passive"))
      (node (ref "RP15D") (pin "4") (pinfunction "R4_4") (pintype "passive"))
    )
    (net (code "77") (name "VTT_REF") (class "Default")
      (node (ref "C10D") (pin "2") (pinfunction "2_2") (pintype "passive"))
      (node (ref "C11D") (pin "1") (pinfunction "1_1") (pintype "passive"))
      (node (ref "C12D") (pin "1") (pinfunction "1_1") (pintype "passive"))
      (node (ref "C30D") (pin "2") (pinfunction "2_2") (pintype "passive"))
      (node (ref "C31D") (pin "1") (pinfunction "1_1") (pintype "passive"))
      (node (ref "C32D") (pin "1") (pinfunction "1_1") (pintype "passive"))
      (node (ref "U10D") (pin "H1") (pinfunction "VREFDQ_H1") (pintype "input"))
      (node (ref "U10D") (pin "M8") (pinfunction "VREFCA_M8") (pintype "input"))
      (node (ref "U11D") (pin "H1") (pinfunction "VREFDQ_H1") (pintype "input"))
      (node (ref "U11D") (pin "M8") (pinfunction "VREFCA_M8") (pintype "input"))
    )
    (net (code "78") (name "unconnected-(RP14D-R12-Pad8)") (class "Default")
      (node (ref "RP14D") (pin "8") (pinfunction "R12_8") (pintype "passive"))
    )
    (net (code "79") (name "unconnected-(U10DC-NC-PadJ1)") (class "Default")
      (node (ref "U10D") (pin "J1") (pinfunction "NC_J1") (pintype "passive+no_connect"))
    )
    (net (code "80") (name "unconnected-(U10DC-NC-PadJ9)") (class "Default")
      (node (ref "U10D") (pin "J9") (pinfunction "NC_J9") (pintype "passive+no_connect"))
    )
    (net (code "81") (name "unconnected-(U10DC-NC-PadL1)") (class "Default")
      (node (ref "U10D") (pin "L1") (pinfunction "NC_L1") (pintype "passive+no_connect"))
    )
    (net (code "82") (name "unconnected-(U10DC-NC-PadL9)") (class "Default")
      (node (ref "U10D") (pin "L9") (pinfunction "NC_L9") (pintype "passive+no_connect"))
    )
    (net (code "83") (name "unconnected-(U10DC-NC-PadM7)") (class "Default")
      (node (ref "U10D") (pin "M7") (pinfunction "NC_M7") (pintype "passive+no_connect"))
    )
    (net (code "84") (name "unconnected-(U10DC-NC-PadT7)") (class "Default")
      (node (ref "U10D") (pin "T7") (pinfunction "NC_T7") (pintype "passive+no_connect"))
    )
    (net (code "85") (name "unconnected-(U11DC-NC-PadJ1)") (class "Default")
      (node (ref "U11D") (pin "J1") (pinfunction "NC_J1") (pintype "passive+no_connect"))
    )
    (net (code "86") (name "unconnected-(U11DC-NC-PadJ9)") (class "Default")
      (node (ref "U11D") (pin "J9") (pinfunction "NC_J9") (pintype "passive+no_connect"))
    )
    (net (code "87") (name "unconnected-(U11DC-NC-PadL1)") (class "Default")
      (node (ref "U11D") (pin "L1") (pinfunction "NC_L1") (pintype "passive+no_connect"))
    )
    (net (code "88") (name "unconnected-(U11DC-NC-PadL9)") (class "Default")
      (node (ref "U11D") (pin "L9") (pinfunction "NC_L9") (pintype "passive+no_connect"))
    )
    (net (code "89") (name "unconnected-(U11DC-NC-PadM7)") (class "Default")
      (node (ref "U11D") (pin "M7") (pinfunction "NC_M7") (pintype "passive+no_connect"))
    )
    (net (code "90") (name "unconnected-(U11DC-NC-PadT7)") (class "Default")
      (node (ref "U11D") (pin "T7") (pinfunction "NC_T7") (pintype "passive+no_connect"))
    )
  )
)
